# Schema_IOT_v0_3.net
KiCad netlist of a schematic drawn in EAGLE
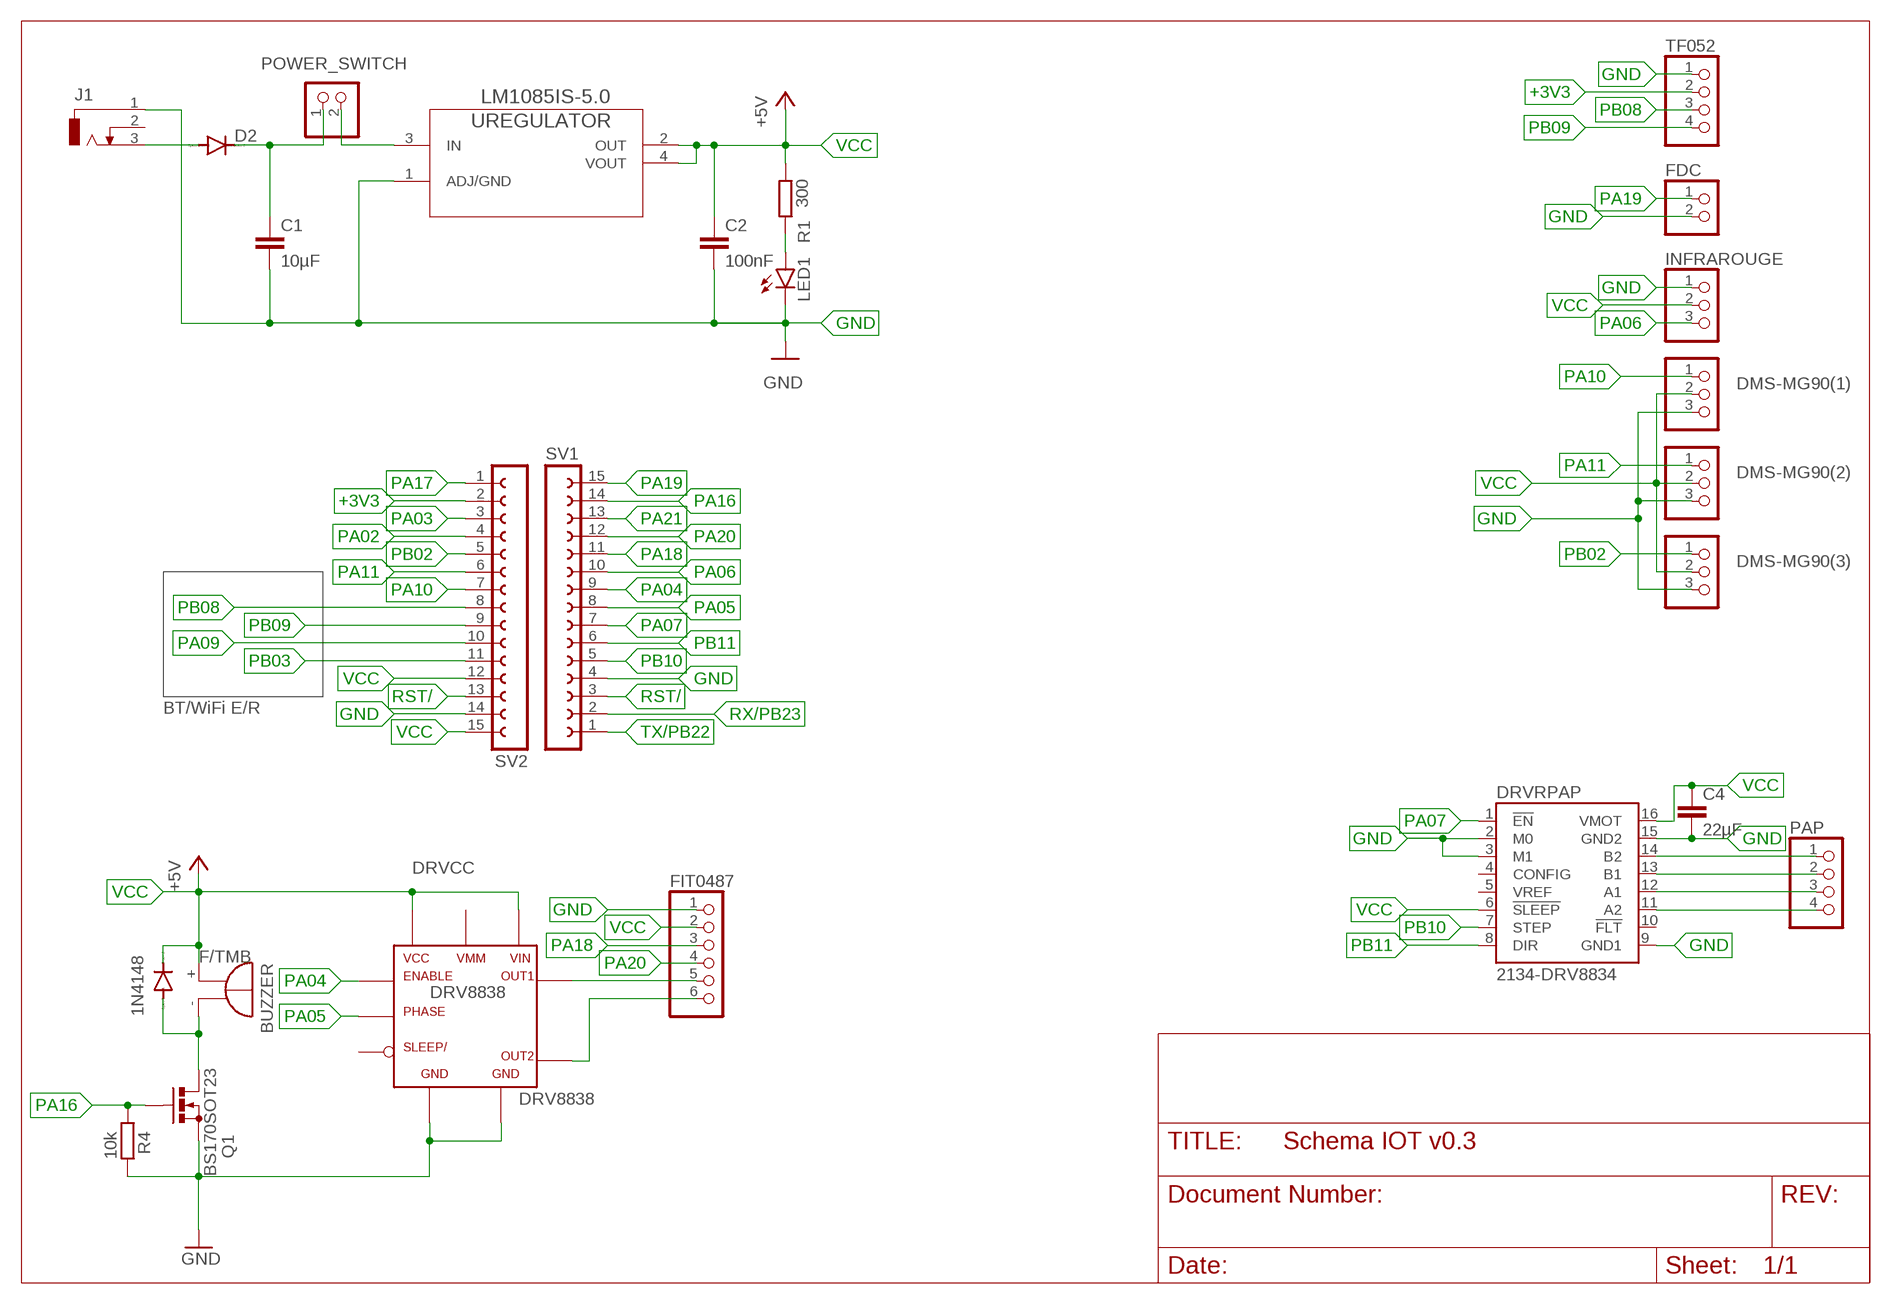
[diagram p0: schematic, sheet 1]

(export (version "E")
  (design (tool "Eeschema 10.0.6"))
  (components
    (comp (ref "BUZZER")
      (value "F/TMB")
      (footprint "eagle-import:F_TMB")
      (libsource (lib "eagle-import") (part "F/TMB"))
    )
    (comp (ref "C1")
      (value "10µF")
      (footprint "eagle-import:C1206")
      (libsource (lib "eagle-import") (part "C-EUC1206"))
    )
    (comp (ref "C2")
      (value "100nF")
      (footprint "eagle-import:C1206")
      (libsource (lib "eagle-import") (part "C-EUC1206"))
    )
    (comp (ref "C4")
      (value "22µF")
      (footprint "eagle-import:C025-050X050")
      (libsource (lib "eagle-import") (part "C-EU025-050X050"))
    )
    (comp (ref "D1")
      (value "1N4148")
      (footprint "eagle-import:SOD-123_MINI-SMA")
      (libsource (lib "eagle-import") (part "1N4148"))
    )
    (comp (ref "D2")
      (value "DIODE-DO214AC")
      (footprint "eagle-import:DO214AC")
      (libsource (lib "eagle-import") (part "DIODE-DO214AC"))
    )
    (comp (ref "DMS-MG90(1)")
      (value "PINHD-1X3")
      (footprint "eagle-import:1X03")
      (libsource (lib "eagle-import") (part "PINHD-1X3"))
    )
    (comp (ref "DMS-MG90(2)")
      (value "PINHD-1X3")
      (footprint "eagle-import:1X03")
      (libsource (lib "eagle-import") (part "PINHD-1X3"))
    )
    (comp (ref "DMS-MG90(3)")
      (value "PINHD-1X3")
      (footprint "eagle-import:1X03")
      (libsource (lib "eagle-import") (part "PINHD-1X3"))
    )
    (comp (ref "DRVCC")
      (value "DRV8838")
      (footprint "eagle-import:DRV8838")
      (libsource (lib "eagle-import") (part "DRV8838"))
    )
    (comp (ref "DRVRPAP")
      (value "2134-DRV8834")
      (footprint "eagle-import:DRV8834")
      (libsource (lib "eagle-import") (part "2134-DRV8834"))
    )
    (comp (ref "FDC")
      (value "PINHD-1X2")
      (footprint "eagle-import:1X02")
      (libsource (lib "eagle-import") (part "PINHD-1X2"))
    )
    (comp (ref "FIT0487")
      (value "PINHD-1X6")
      (footprint "eagle-import:1X06")
      (libsource (lib "eagle-import") (part "PINHD-1X6"))
    )
    (comp (ref "INFRAROUGE")
      (value "PINHD-1X3")
      (footprint "eagle-import:1X03")
      (libsource (lib "eagle-import") (part "PINHD-1X3"))
    )
    (comp (ref "J1")
      (value "DCJ0303")
      (footprint "eagle-import:DCJ0303")
      (libsource (lib "eagle-import") (part "DCJ0303"))
    )
    (comp (ref "LED1")
      (value "LED5MM")
      (footprint "eagle-import:LED5MM")
      (libsource (lib "eagle-import") (part "LED5MM"))
    )
    (comp (ref "PAP")
      (value "PINHD-1X4")
      (footprint "eagle-import:1X04")
      (libsource (lib "eagle-import") (part "PINHD-1X4"))
    )
    (comp (ref "POWER_SWITCH")
      (value "PINHD-1X2")
      (footprint "eagle-import:1X02")
      (libsource (lib "eagle-import") (part "PINHD-1X2"))
    )
    (comp (ref "Q1")
      (value "BS170SOT23")
      (footprint "eagle-import:SOT23")
      (libsource (lib "eagle-import") (part "BS170SOT23"))
    )
    (comp (ref "R1")
      (value "300")
      (footprint "eagle-import:R1206")
      (libsource (lib "eagle-import") (part "R-EU_R1206"))
    )
    (comp (ref "R4")
      (value "10k")
      (footprint "eagle-import:R1206")
      (libsource (lib "eagle-import") (part "R-EU_R1206"))
    )
    (comp (ref "SV1")
      (value "FE15-1")
      (footprint "eagle-import:FE15")
      (libsource (lib "eagle-import") (part "FE15-1"))
    )
    (comp (ref "SV2")
      (value "FE15-1")
      (footprint "eagle-import:FE15")
      (libsource (lib "eagle-import") (part "FE15-1"))
    )
    (comp (ref "TF052")
      (value "PINHD-1X4")
      (footprint "eagle-import:1X04")
      (libsource (lib "eagle-import") (part "PINHD-1X4"))
    )
    (comp (ref "UREGULATOR")
      (value "LM1085IS-5.0")
      (footprint "eagle-import:TO254P1435X457-3N")
      (fields (field (name "MF") "Texas Instruments"))
      (libsource (lib "eagle-import") (part "LM1085IS-5.0"))
    )
  )
  (nets
    (net (code "1") (name "+3V3") (class "Default")
      (node (ref "SV2") (pin "2") (pinfunction "2_2") (pintype "passive"))
      (node (ref "TF052") (pin "2") (pinfunction "2_2") (pintype "passive"))
    )
    (net (code "2") (name "GND") (class "Default")
      (node (ref "C1") (pin "2") (pinfunction "2_2") (pintype "passive"))
      (node (ref "C2") (pin "2") (pinfunction "2_2") (pintype "passive"))
      (node (ref "C4") (pin "2") (pinfunction "2_2") (pintype "passive"))
      (node (ref "DMS-MG90(1)") (pin "3") (pinfunction "3_3") (pintype "passive"))
      (node (ref "DMS-MG90(2)") (pin "3") (pinfunction "3_3") (pintype "passive"))
      (node (ref "DMS-MG90(3)") (pin "3") (pinfunction "3_3") (pintype "passive"))
      (node (ref "DRVCC") (pin "GND1") (pinfunction "GND1_GND1") (pintype "power_in"))
      (node (ref "DRVCC") (pin "GND2") (pinfunction "GND2_GND2") (pintype "power_in"))
      (node (ref "DRVRPAP") (pin "15") (pinfunction "GND2_15") (pintype "power_in"))
      (node (ref "DRVRPAP") (pin "2") (pinfunction "M0_2") (pintype "passive"))
      (node (ref "DRVRPAP") (pin "3") (pinfunction "M1_3") (pintype "passive"))
      (node (ref "DRVRPAP") (pin "9") (pinfunction "GND1_9") (pintype "power_in"))
      (node (ref "FDC") (pin "2") (pinfunction "2_2") (pintype "passive"))
      (node (ref "FIT0487") (pin "1") (pinfunction "1_1") (pintype "passive"))
      (node (ref "INFRAROUGE") (pin "1") (pinfunction "1_1") (pintype "passive"))
      (node (ref "J1") (pin "1") (pinfunction "1_1") (pintype "passive"))
      (node (ref "LED1") (pin "K") (pinfunction "C_K") (pintype "passive"))
      (node (ref "Q1") (pin "2") (pinfunction "S_2") (pintype "passive"))
      (node (ref "R4") (pin "2") (pinfunction "2_2") (pintype "passive"))
      (node (ref "SV1") (pin "4") (pinfunction "4_4") (pintype "passive"))
      (node (ref "SV2") (pin "14") (pinfunction "14_14") (pintype "passive"))
      (node (ref "TF052") (pin "1") (pinfunction "1_1") (pintype "passive"))
      (node (ref "UREGULATOR") (pin "1") (pinfunction "ADJ/GND_1") (pintype "passive"))
    )
    (net (code "3") (name "Net-(C1-Pad1)") (class "Default")
      (node (ref "C1") (pin "1") (pinfunction "1_1") (pintype "passive"))
      (node (ref "D2") (pin "C") (pinfunction "C_C") (pintype "passive"))
      (node (ref "POWER_SWITCH") (pin "1") (pinfunction "1_1") (pintype "passive"))
    )
    (net (code "4") (name "Net-(D2-PadA)") (class "Default")
      (node (ref "D2") (pin "A") (pinfunction "A_A") (pintype "passive"))
      (node (ref "J1") (pin "3") (pinfunction "3_3") (pintype "passive"))
    )
    (net (code "5") (name "Net-(DRVCC-PadOUT1)") (class "Default")
      (node (ref "DRVCC") (pin "OUT1") (pinfunction "OUT1_OUT1") (pintype "output"))
      (node (ref "FIT0487") (pin "5") (pinfunction "5_5") (pintype "passive"))
    )
    (net (code "6") (name "Net-(DRVCC-PadOUT2)") (class "Default")
      (node (ref "DRVCC") (pin "OUT2") (pinfunction "OUT2_OUT2") (pintype "output"))
      (node (ref "FIT0487") (pin "6") (pinfunction "6_6") (pintype "passive"))
    )
    (net (code "7") (name "Net-(DRVRPAP-A1)") (class "Default")
      (node (ref "DRVRPAP") (pin "12") (pinfunction "A1_12") (pintype "output"))
      (node (ref "PAP") (pin "3") (pinfunction "3_3") (pintype "passive"))
    )
    (net (code "8") (name "Net-(DRVRPAP-A2)") (class "Default")
      (node (ref "DRVRPAP") (pin "11") (pinfunction "A2_11") (pintype "output"))
      (node (ref "PAP") (pin "4") (pinfunction "4_4") (pintype "passive"))
    )
    (net (code "9") (name "Net-(DRVRPAP-B1)") (class "Default")
      (node (ref "DRVRPAP") (pin "13") (pinfunction "B1_13") (pintype "output"))
      (node (ref "PAP") (pin "2") (pinfunction "2_2") (pintype "passive"))
    )
    (net (code "10") (name "Net-(DRVRPAP-B2)") (class "Default")
      (node (ref "DRVRPAP") (pin "14") (pinfunction "B2_14") (pintype "output"))
      (node (ref "PAP") (pin "1") (pinfunction "1_1") (pintype "passive"))
    )
    (net (code "11") (name "Net-(LED1-PadA)") (class "Default")
      (node (ref "LED1") (pin "A") (pinfunction "A_A") (pintype "passive"))
      (node (ref "R1") (pin "1") (pinfunction "1_1") (pintype "passive"))
    )
    (net (code "12") (name "Net-(Q1-D)") (class "Default")
      (node (ref "BUZZER") (pin "-") (pinfunction "-_-") (pintype "passive"))
      (node (ref "D1") (pin "A") (pinfunction "A_A") (pintype "passive"))
      (node (ref "Q1") (pin "3") (pinfunction "D_3") (pintype "passive"))
    )
    (net (code "13") (name "Net-(UREGULATOR-IN)") (class "Default")
      (node (ref "POWER_SWITCH") (pin "2") (pinfunction "2_2") (pintype "passive"))
      (node (ref "UREGULATOR") (pin "3") (pinfunction "IN_3") (pintype "power_in"))
    )
    (net (code "14") (name "PA02") (class "Default")
      (node (ref "SV2") (pin "4") (pinfunction "4_4") (pintype "passive"))
    )
    (net (code "15") (name "PA03") (class "Default")
      (node (ref "SV2") (pin "3") (pinfunction "3_3") (pintype "passive"))
    )
    (net (code "16") (name "PA04") (class "Default")
      (node (ref "DRVCC") (pin "ENABLE") (pinfunction "ENABLE_ENABLE") (pintype "input"))
      (node (ref "SV1") (pin "9") (pinfunction "9_9") (pintype "passive"))
    )
    (net (code "17") (name "PA05") (class "Default")
      (node (ref "DRVCC") (pin "PHASE") (pinfunction "PHASE_PHASE") (pintype "input"))
      (node (ref "SV1") (pin "8") (pinfunction "8_8") (pintype "passive"))
    )
    (net (code "18") (name "PA06") (class "Default")
      (node (ref "INFRAROUGE") (pin "3") (pinfunction "3_3") (pintype "passive"))
      (node (ref "SV1") (pin "10") (pinfunction "10_10") (pintype "passive"))
    )
    (net (code "19") (name "PA07") (class "Default")
      (node (ref "DRVRPAP") (pin "1") (pinfunction "~{EN}_1") (pintype "passive"))
      (node (ref "SV1") (pin "7") (pinfunction "7_7") (pintype "passive"))
    )
    (net (code "20") (name "PA09") (class "Default")
      (node (ref "SV2") (pin "10") (pinfunction "10_10") (pintype "passive"))
    )
    (net (code "21") (name "PA10") (class "Default")
      (node (ref "DMS-MG90(1)") (pin "1") (pinfunction "1_1") (pintype "passive"))
      (node (ref "SV2") (pin "7") (pinfunction "7_7") (pintype "passive"))
    )
    (net (code "22") (name "PA11") (class "Default")
      (node (ref "DMS-MG90(2)") (pin "1") (pinfunction "1_1") (pintype "passive"))
      (node (ref "SV2") (pin "6") (pinfunction "6_6") (pintype "passive"))
    )
    (net (code "23") (name "PA16") (class "Default")
      (node (ref "Q1") (pin "1") (pinfunction "G_1") (pintype "passive"))
      (node (ref "R4") (pin "1") (pinfunction "1_1") (pintype "passive"))
      (node (ref "SV1") (pin "14") (pinfunction "14_14") (pintype "passive"))
    )
    (net (code "24") (name "PA17") (class "Default")
      (node (ref "SV2") (pin "1") (pinfunction "1_1") (pintype "passive"))
    )
    (net (code "25") (name "PA18") (class "Default")
      (node (ref "FIT0487") (pin "3") (pinfunction "3_3") (pintype "passive"))
      (node (ref "SV1") (pin "11") (pinfunction "11_11") (pintype "passive"))
    )
    (net (code "26") (name "PA19") (class "Default")
      (node (ref "FDC") (pin "1") (pinfunction "1_1") (pintype "passive"))
      (node (ref "SV1") (pin "15") (pinfunction "15_15") (pintype "passive"))
    )
    (net (code "27") (name "PA20") (class "Default")
      (node (ref "FIT0487") (pin "4") (pinfunction "4_4") (pintype "passive"))
      (node (ref "SV1") (pin "12") (pinfunction "12_12") (pintype "passive"))
    )
    (net (code "28") (name "PA21") (class "Default")
      (node (ref "SV1") (pin "13") (pinfunction "13_13") (pintype "passive"))
    )
    (net (code "29") (name "PB02") (class "Default")
      (node (ref "DMS-MG90(3)") (pin "1") (pinfunction "1_1") (pintype "passive"))
      (node (ref "SV2") (pin "5") (pinfunction "5_5") (pintype "passive"))
    )
    (net (code "30") (name "PB03") (class "Default")
      (node (ref "SV2") (pin "11") (pinfunction "11_11") (pintype "passive"))
    )
    (net (code "31") (name "PB08") (class "Default")
      (node (ref "SV2") (pin "8") (pinfunction "8_8") (pintype "passive"))
      (node (ref "TF052") (pin "3") (pinfunction "3_3") (pintype "passive"))
    )
    (net (code "32") (name "PB09") (class "Default")
      (node (ref "SV2") (pin "9") (pinfunction "9_9") (pintype "passive"))
      (node (ref "TF052") (pin "4") (pinfunction "4_4") (pintype "passive"))
    )
    (net (code "33") (name "PB10") (class "Default")
      (node (ref "DRVRPAP") (pin "7") (pinfunction "STEP_7") (pintype "input"))
      (node (ref "SV1") (pin "5") (pinfunction "5_5") (pintype "passive"))
    )
    (net (code "34") (name "PB11") (class "Default")
      (node (ref "DRVRPAP") (pin "8") (pinfunction "DIR_8") (pintype "input"))
      (node (ref "SV1") (pin "6") (pinfunction "6_6") (pintype "passive"))
    )
    (net (code "35") (name "RST{slash}") (class "Default")
      (node (ref "SV1") (pin "3") (pinfunction "3_3") (pintype "passive"))
      (node (ref "SV2") (pin "13") (pinfunction "13_13") (pintype "passive"))
    )
    (net (code "36") (name "RX{slash}PB23") (class "Default")
      (node (ref "SV1") (pin "2") (pinfunction "2_2") (pintype "passive"))
    )
    (net (code "37") (name "TX{slash}PB22") (class "Default")
      (node (ref "SV1") (pin "1") (pinfunction "1_1") (pintype "passive"))
    )
    (net (code "38") (name "VCC") (class "Default")
      (node (ref "BUZZER") (pin "+") (pinfunction "+_+") (pintype "passive"))
      (node (ref "C2") (pin "1") (pinfunction "1_1") (pintype "passive"))
      (node (ref "C4") (pin "1") (pinfunction "1_1") (pintype "passive"))
      (node (ref "D1") (pin "C") (pinfunction "C_C") (pintype "passive"))
      (node (ref "DMS-MG90(1)") (pin "2") (pinfunction "2_2") (pintype "passive"))
      (node (ref "DMS-MG90(2)") (pin "2") (pinfunction "2_2") (pintype "passive"))
      (node (ref "DMS-MG90(3)") (pin "2") (pinfunction "2_2") (pintype "passive"))
      (node (ref "DRVCC") (pin "VCC") (pinfunction "VCC_VCC") (pintype "power_in"))
      (node (ref "DRVCC") (pin "VIN") (pinfunction "VIN_VIN") (pintype "power_in"))
      (node (ref "DRVRPAP") (pin "16") (pinfunction "VMOT_16") (pintype "power_in"))
      (node (ref "DRVRPAP") (pin "6") (pinfunction "~{SLEEP}_6") (pintype "input"))
      (node (ref "FIT0487") (pin "2") (pinfunction "2_2") (pintype "passive"))
      (node (ref "INFRAROUGE") (pin "2") (pinfunction "2_2") (pintype "passive"))
      (node (ref "R1") (pin "2") (pinfunction "2_2") (pintype "passive"))
      (node (ref "SV2") (pin "12") (pinfunction "12_12") (pintype "passive"))
      (node (ref "SV2") (pin "15") (pinfunction "15_15") (pintype "passive"))
      (node (ref "UREGULATOR") (pin "2") (pinfunction "OUT_2") (pintype "output"))
      (node (ref "UREGULATOR") (pin "4") (pinfunction "VOUT_4") (pintype "output"))
    )
    (net (code "39") (name "unconnected-(DRVCC-PadSLEEP{slash})") (class "Default")
      (node (ref "DRVCC") (pin "SLEEP/") (pinfunction "SLEEP/_SLEEP/") (pintype "bidirectional"))
    )
    (net (code "40") (name "unconnected-(DRVCC-PadVMM)") (class "Default")
      (node (ref "DRVCC") (pin "VMM") (pinfunction "VMM_VMM") (pintype "no_connect"))
    )
    (net (code "41") (name "unconnected-(DRVRPAP-CONFIG-Pad4)") (class "Default")
      (node (ref "DRVRPAP") (pin "4") (pinfunction "CONFIG_4") (pintype "passive"))
    )
    (net (code "42") (name "unconnected-(DRVRPAP-VREF-Pad5)") (class "Default")
      (node (ref "DRVRPAP") (pin "5") (pinfunction "VREF_5") (pintype "passive"))
    )
    (net (code "43") (name "unconnected-(DRVRPAP-~{FLT}-Pad10)") (class "Default")
      (node (ref "DRVRPAP") (pin "10") (pinfunction "~{FLT}_10") (pintype "open_collector"))
    )
    (net (code "44") (name "unconnected-(J1-Pad2)") (class "Default")
      (node (ref "J1") (pin "2") (pinfunction "2_2") (pintype "passive"))
    )
  )
)
